# schematic_sheet2.net
KiCad netlist of a schematic drawn in Altium Designer
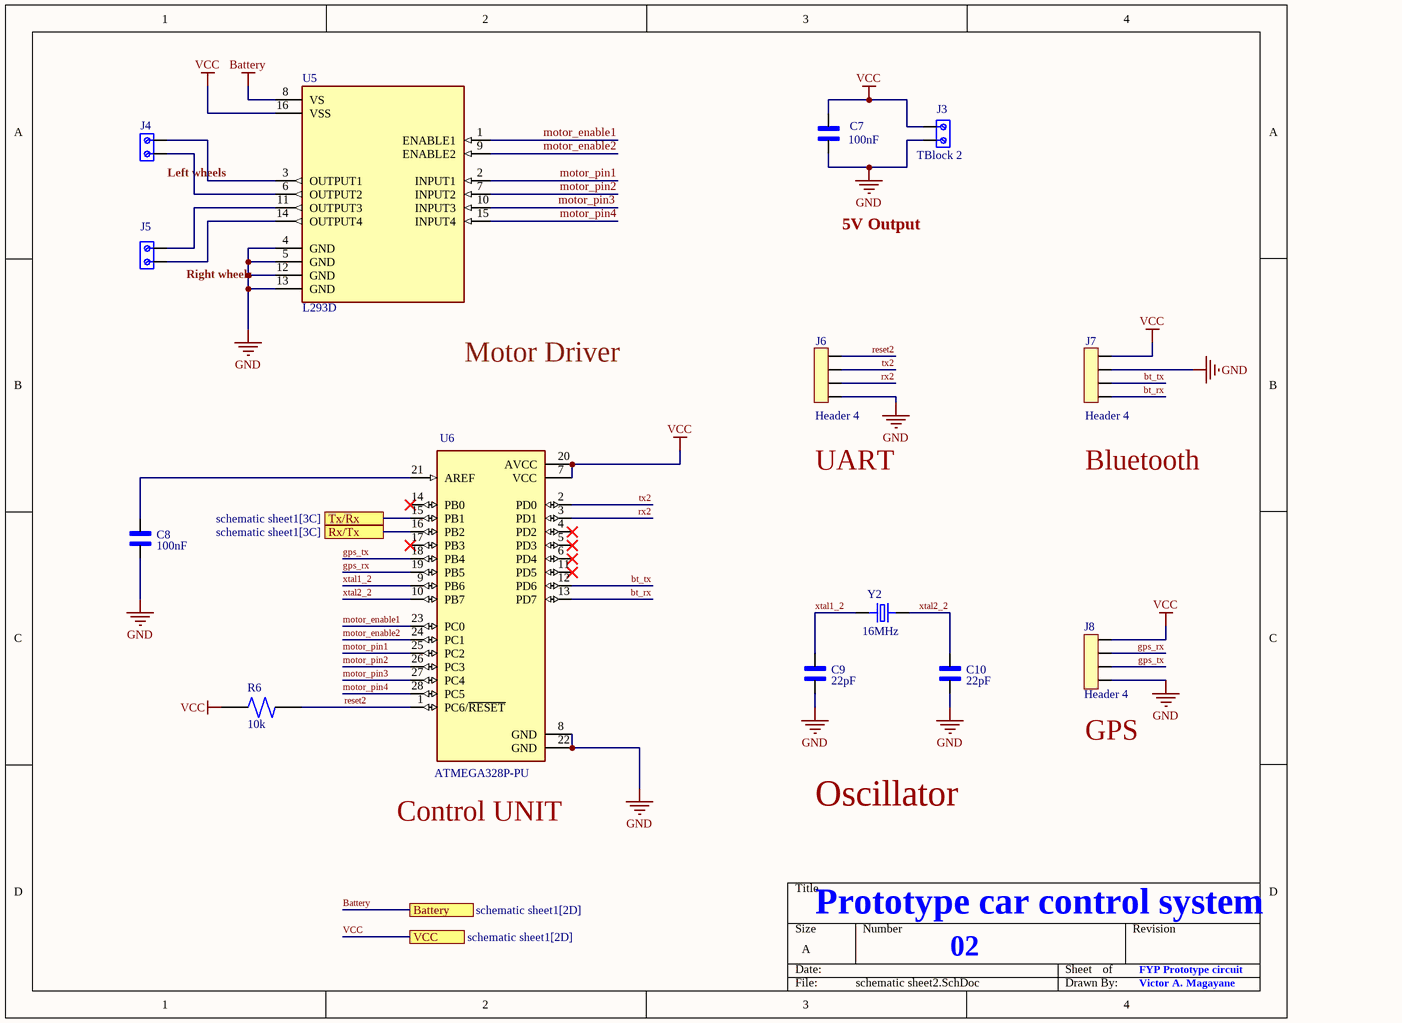
[diagram p0: schematic sheet2.SchDoc]

(export (version "E")
  (design (tool "Eeschema 10.0.6"))
  (components
    (comp (ref "C7")
      (value "100nF")
      (footprint "CAPRB500W50L450T300H550")
      (description "2200 pF Â±10% 250V Ceramic Capacitor X7R Radial")
      (fields (field (name "DIGI-KEY_PART_NUMBER") "445-173386-1-ND") (field (name "MF") "TDK"))
      (libsource (lib "") (part "Ceramic capacitor_1"))
    )
    (comp (ref "C8")
      (value "100nF")
      (footprint "CAPRB500W50L450T300H550")
      (description "2200 pF Â±10% 250V Ceramic Capacitor X7R Radial")
      (fields (field (name "DIGI-KEY_PART_NUMBER") "445-173386-1-ND") (field (name "MF") "TDK"))
      (libsource (lib "Installed library") (part "Ceramic capacitor"))
    )
    (comp (ref "C9")
      (value "22pF")
      (footprint "CAPRB500W50L450T300H550")
      (description "2200 pF Â±10% 250V Ceramic Capacitor X7R Radial")
      (fields (field (name "DIGI-KEY_PART_NUMBER") "445-173386-1-ND") (field (name "MF") "TDK"))
      (libsource (lib "Installed library") (part "Ceramic capacitor"))
    )
    (comp (ref "C10")
      (value "22pF")
      (footprint "CAPRB500W50L450T300H550")
      (description "2200 pF Â±10% 250V Ceramic Capacitor X7R Radial")
      (fields (field (name "DIGI-KEY_PART_NUMBER") "445-173386-1-ND") (field (name "MF") "TDK"))
      (libsource (lib "Installed library") (part "Ceramic capacitor"))
    )
    (comp (ref "J3")
      (value "TBlock 2")
      (footprint "691111710002")
      (description "2 Position Wire to Board Terminal Block Horizontal with Board 0.197 _5.00mm_ Through Hole")
      (fields (field (name "MP") "691111710002") (field (name "MF") "Wurth Electronics"))
      (libsource (lib "Installed library") (part "Terminal Block - 2Pins"))
    )
    (comp (ref "J4")
      (value "691111710002")
      (footprint "691111710002")
      (description "2 Position Wire to Board Terminal Block Horizontal with Board 0.197 _5.00mm_ Through Hole")
      (fields (field (name "MF") "Wurth Electronics"))
      (libsource (lib "Installed library") (part "Terminal Block - 2Pins"))
    )
    (comp (ref "J5")
      (value "691111710002")
      (footprint "691111710002")
      (description "2 Position Wire to Board Terminal Block Horizontal with Board 0.197 _5.00mm_ Through Hole")
      (fields (field (name "MF") "Wurth Electronics"))
      (libsource (lib "Installed library") (part "Terminal Block - 2Pins"))
    )
    (comp (ref "J6")
      (value "Header 4")
      (footprint "SULLINS_PPTC041LFBN-RC")
      (description "4 Position Header Connector Through Hole")
      (fields (field (name "MP") "PPTC041LFBN-RC") (field (name "MF") "Sullins Connector"))
      (libsource (lib "Installed library") (part "Female header - 4Pins"))
    )
    (comp (ref "J7")
      (value "Header 4")
      (footprint "SULLINS_PPTC041LFBN-RC")
      (description "4 Position Header Connector Through Hole")
      (fields (field (name "MP") "PPTC041LFBN-RC") (field (name "MF") "Sullins Connector"))
      (libsource (lib "Installed library") (part "Female header - 4Pins"))
    )
    (comp (ref "J8")
      (value "Header 4")
      (footprint "SULLINS_PPTC041LFBN-RC")
      (description "4 Position Header Connector Through Hole")
      (fields (field (name "MP") "PPTC041LFBN-RC") (field (name "MF") "Sullins Connector"))
      (libsource (lib "") (part "Female header - 4Pins_1"))
    )
    (comp (ref "R6")
      (value "10k")
      (footprint "RESAD1100W55L680D260")
      (description "(MFR-25FBF52-10K) 10,2 kOhm bei 1% 0,25W, 1/4W Durchbohrlochwiderstand Axial Metal Film")
      (fields (field (name "DIGI-KEY_PART_NUMBER") "10.2KXBK-ND") (field (name "MF") "Yageo"))
      (libsource (lib "Installed library") (part "Resistor (0.25W)"))
    )
    (comp (ref "U5")
      (value "L293D")
      (footprint "DIP880W50P254L2000H510Q16")
      (description "4-Channel Motor Driver 24V 16-Pin Power PDIP Tube")
      (libsource (lib "Installed library") (part "L293D"))
    )
    (comp (ref "U6")
      (value "ATMEGA328P-PU")
      (footprint "DIP794W46P254L2967H457Q28B")
      (description "ATmega Series 20 MHz 32 KB Flash 2 KB SRAM 8-Bit Microcontroller - DIP-28")
      (libsource (lib "Installed library") (part "ATMEGA328P-PU"))
    )
    (comp (ref "Y2")
      (value "16MHz")
      (footprint "XTAL_ECS-160-20-4X")
      (description "CRYSTAL T/H")
      (fields (field (name "MF") "{'manufacturer': u'ECS Inc.'}") (field (name "MP") "ECS-160-S-4"))
      (libsource (lib "Installed library") (part "Crystal oscilator"))
    )
  )
  (nets
    (net (code "1") (name "/Rx{slash}Tx") (class "Default")
      (node (ref "U6") (pin "16") (pinfunction "PB2_16") (pintype "bidirectional"))
    )
    (net (code "2") (name "/Tx{slash}Rx") (class "Default")
      (node (ref "U6") (pin "15") (pinfunction "PB1_15") (pintype "bidirectional"))
    )
    (net (code "3") (name "/bt_rx") (class "Default")
      (node (ref "J7") (pin "4") (pinfunction "4_4") (pintype "passive"))
      (node (ref "U6") (pin "13") (pinfunction "PD7_13") (pintype "bidirectional"))
    )
    (net (code "4") (name "/bt_tx") (class "Default")
      (node (ref "J7") (pin "3") (pinfunction "3_3") (pintype "passive"))
      (node (ref "U6") (pin "12") (pinfunction "PD6_12") (pintype "bidirectional"))
    )
    (net (code "5") (name "/gps_rx") (class "Default")
      (node (ref "J8") (pin "3") (pinfunction "3_3") (pintype "passive"))
      (node (ref "U6") (pin "19") (pinfunction "PB5_19") (pintype "bidirectional"))
    )
    (net (code "6") (name "/gps_tx") (class "Default")
      (node (ref "J8") (pin "2") (pinfunction "2_2") (pintype "passive"))
      (node (ref "U6") (pin "18") (pinfunction "PB4_18") (pintype "bidirectional"))
    )
    (net (code "7") (name "/motor_enable1") (class "Default")
      (node (ref "U5") (pin "1") (pinfunction "ENABLE1_1") (pintype "input"))
      (node (ref "U6") (pin "23") (pinfunction "PC0_23") (pintype "bidirectional"))
    )
    (net (code "8") (name "/motor_enable2") (class "Default")
      (node (ref "U5") (pin "9") (pinfunction "ENABLE2_9") (pintype "input"))
      (node (ref "U6") (pin "24") (pinfunction "PC1_24") (pintype "bidirectional"))
    )
    (net (code "9") (name "/motor_pin1") (class "Default")
      (node (ref "U5") (pin "2") (pinfunction "INPUT1_2") (pintype "input"))
      (node (ref "U6") (pin "25") (pinfunction "PC2_25") (pintype "bidirectional"))
    )
    (net (code "10") (name "/motor_pin2") (class "Default")
      (node (ref "U5") (pin "7") (pinfunction "INPUT2_7") (pintype "input"))
      (node (ref "U6") (pin "26") (pinfunction "PC3_26") (pintype "bidirectional"))
    )
    (net (code "11") (name "/motor_pin3") (class "Default")
      (node (ref "U5") (pin "10") (pinfunction "INPUT3_10") (pintype "input"))
      (node (ref "U6") (pin "27") (pinfunction "PC4_27") (pintype "bidirectional"))
    )
    (net (code "12") (name "/motor_pin4") (class "Default")
      (node (ref "U5") (pin "15") (pinfunction "INPUT4_15") (pintype "input"))
      (node (ref "U6") (pin "28") (pinfunction "PC5_28") (pintype "bidirectional"))
    )
    (net (code "13") (name "/reset2") (class "Default")
      (node (ref "J6") (pin "1") (pinfunction "1_1") (pintype "passive"))
      (node (ref "R6") (pin "2") (pinfunction "2_2") (pintype "passive"))
      (node (ref "U6") (pin "1") (pinfunction "PC6/~{RESET}_1") (pintype "bidirectional"))
    )
    (net (code "14") (name "/rx2") (class "Default")
      (node (ref "J6") (pin "3") (pinfunction "3_3") (pintype "passive"))
      (node (ref "U6") (pin "3") (pinfunction "PD1_3") (pintype "bidirectional"))
    )
    (net (code "15") (name "/tx2") (class "Default")
      (node (ref "J6") (pin "2") (pinfunction "2_2") (pintype "passive"))
      (node (ref "U6") (pin "2") (pinfunction "PD0_2") (pintype "bidirectional"))
    )
    (net (code "16") (name "/xtal1_2") (class "Default")
      (node (ref "C9") (pin "1") (pinfunction "1_1") (pintype "passive"))
      (node (ref "U6") (pin "9") (pinfunction "PB6_9") (pintype "bidirectional"))
      (node (ref "Y2") (pin "1") (pinfunction "1_1") (pintype "passive"))
    )
    (net (code "17") (name "/xtal2_2") (class "Default")
      (node (ref "C10") (pin "1") (pinfunction "1_1") (pintype "passive"))
      (node (ref "U6") (pin "10") (pinfunction "PB7_10") (pintype "bidirectional"))
      (node (ref "Y2") (pin "2") (pinfunction "2_2") (pintype "passive"))
    )
    (net (code "18") (name "Battery") (class "Default")
      (node (ref "U5") (pin "8") (pinfunction "VS_8") (pintype "power_in"))
    )
    (net (code "19") (name "GND") (class "Default")
      (node (ref "C10") (pin "2") (pinfunction "2_2") (pintype "passive"))
      (node (ref "C7") (pin "1") (pinfunction "1_1") (pintype "passive"))
      (node (ref "C8") (pin "2") (pinfunction "2_2") (pintype "passive"))
      (node (ref "C9") (pin "2") (pinfunction "2_2") (pintype "passive"))
      (node (ref "J3") (pin "2") (pinfunction "2_2") (pintype "passive"))
      (node (ref "J6") (pin "4") (pinfunction "4_4") (pintype "passive"))
      (node (ref "J7") (pin "2") (pinfunction "2_2") (pintype "passive"))
      (node (ref "J8") (pin "1") (pinfunction "1_1") (pintype "passive"))
      (node (ref "U5") (pin "12") (pinfunction "GND_12") (pintype "power_in"))
      (node (ref "U5") (pin "13") (pinfunction "GND_13") (pintype "power_in"))
      (node (ref "U5") (pin "4") (pinfunction "GND_4") (pintype "power_in"))
      (node (ref "U5") (pin "5") (pinfunction "GND_5") (pintype "power_in"))
      (node (ref "U6") (pin "22") (pinfunction "GND_22") (pintype "power_in"))
      (node (ref "U6") (pin "8") (pinfunction "GND_8") (pintype "power_in"))
    )
    (net (code "20") (name "Net-(U5-OUTPUT1)") (class "Default")
      (node (ref "J4") (pin "1") (pinfunction "1_1") (pintype "passive"))
      (node (ref "U5") (pin "3") (pinfunction "OUTPUT1_3") (pintype "output"))
    )
    (net (code "21") (name "Net-(U5-OUTPUT2)") (class "Default")
      (node (ref "J4") (pin "2") (pinfunction "2_2") (pintype "passive"))
      (node (ref "U5") (pin "6") (pinfunction "OUTPUT2_6") (pintype "output"))
    )
    (net (code "22") (name "Net-(U5-OUTPUT3)") (class "Default")
      (node (ref "J5") (pin "1") (pinfunction "1_1") (pintype "passive"))
      (node (ref "U5") (pin "11") (pinfunction "OUTPUT3_11") (pintype "output"))
    )
    (net (code "23") (name "Net-(U5-OUTPUT4)") (class "Default")
      (node (ref "J5") (pin "2") (pinfunction "2_2") (pintype "passive"))
      (node (ref "U5") (pin "14") (pinfunction "OUTPUT4_14") (pintype "output"))
    )
    (net (code "24") (name "Net-(U6-AREF)") (class "Default")
      (node (ref "C8") (pin "1") (pinfunction "1_1") (pintype "passive"))
      (node (ref "U6") (pin "21") (pinfunction "AREF_21") (pintype "input"))
    )
    (net (code "25") (name "VCC") (class "Default")
      (node (ref "C7") (pin "2") (pinfunction "2_2") (pintype "passive"))
      (node (ref "J3") (pin "1") (pinfunction "1_1") (pintype "passive"))
      (node (ref "J7") (pin "1") (pinfunction "1_1") (pintype "passive"))
      (node (ref "J8") (pin "4") (pinfunction "4_4") (pintype "passive"))
      (node (ref "R6") (pin "1") (pinfunction "1_1") (pintype "passive"))
      (node (ref "U5") (pin "16") (pinfunction "VSS_16") (pintype "power_in"))
      (node (ref "U6") (pin "20") (pinfunction "AVCC_20") (pintype "power_in"))
      (node (ref "U6") (pin "7") (pinfunction "VCC_7") (pintype "power_in"))
    )
    (net (code "26") (name "unconnected-(U6-PB0-Pad14)") (class "Default")
      (node (ref "U6") (pin "14") (pinfunction "PB0_14") (pintype "bidirectional+no_connect"))
    )
    (net (code "27") (name "unconnected-(U6-PB3-Pad17)") (class "Default")
      (node (ref "U6") (pin "17") (pinfunction "PB3_17") (pintype "bidirectional+no_connect"))
    )
    (net (code "28") (name "unconnected-(U6-PD2-Pad4)") (class "Default")
      (node (ref "U6") (pin "4") (pinfunction "PD2_4") (pintype "bidirectional+no_connect"))
    )
    (net (code "29") (name "unconnected-(U6-PD3-Pad5)") (class "Default")
      (node (ref "U6") (pin "5") (pinfunction "PD3_5") (pintype "bidirectional+no_connect"))
    )
    (net (code "30") (name "unconnected-(U6-PD4-Pad6)") (class "Default")
      (node (ref "U6") (pin "6") (pinfunction "PD4_6") (pintype "bidirectional+no_connect"))
    )
    (net (code "31") (name "unconnected-(U6-PD5-Pad11)") (class "Default")
      (node (ref "U6") (pin "11") (pinfunction "PD5_11") (pintype "bidirectional+no_connect"))
    )
  )
)
